# 3DHover.net
KiCad netlist of a schematic drawn in EAGLE
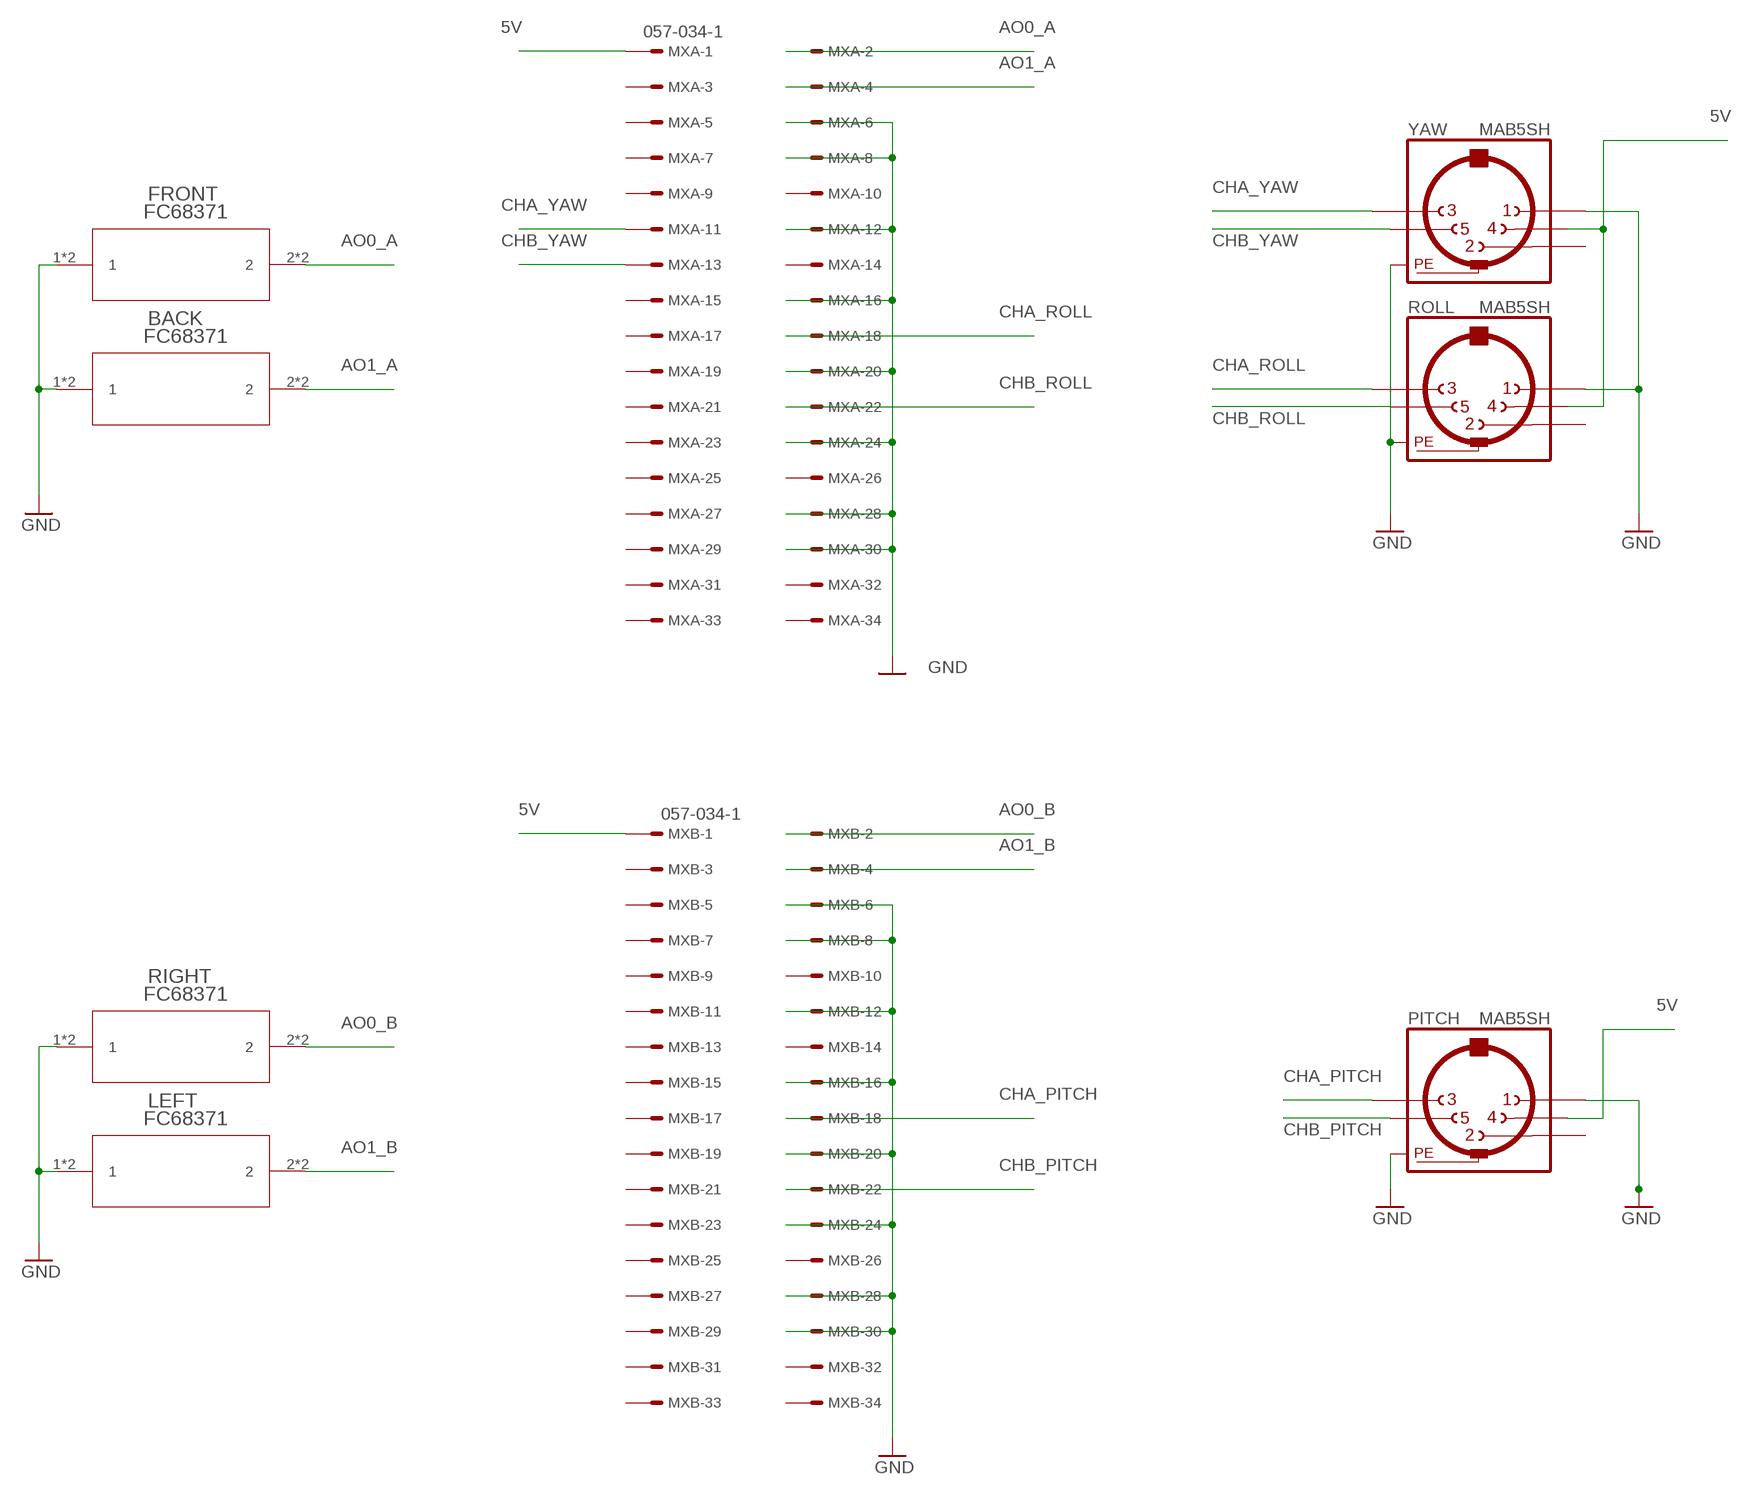
[diagram p0: schematic, sheet 1]

(export (version "E")
  (design (tool "Eeschema 10.0.6"))
  (components
    (comp (ref "BACK")
      (value "FC68371")
      (footprint "eagle-import:FC68371_CLF")
      (fields (field (name "COPYRIGHT") "Copyright (C) 2022 Ultra Librarian. All rights reserved."))
      (libsource (lib "eagle-import") (part "FC68371"))
    )
    (comp (ref "FRONT")
      (value "FC68371")
      (footprint "eagle-import:FC68371_CLF")
      (fields (field (name "COPYRIGHT") "Copyright (C) 2022 Ultra Librarian. All rights reserved."))
      (libsource (lib "eagle-import") (part "FC68371"))
    )
    (comp (ref "LEFT")
      (value "FC68371")
      (footprint "eagle-import:FC68371_CLF")
      (fields (field (name "COPYRIGHT") "Copyright (C) 2022 Ultra Librarian. All rights reserved."))
      (libsource (lib "eagle-import") (part "FC68371"))
    )
    (comp (ref "MXA")
      (value "057-034-1")
      (footprint "eagle-import:057-034-1")
      (libsource (lib "eagle-import") (part "057-034-1"))
    )
    (comp (ref "MXB")
      (value "057-034-1")
      (footprint "eagle-import:057-034-1")
      (libsource (lib "eagle-import") (part "057-034-1"))
    )
    (comp (ref "PITCH")
      (value "MAB5SH")
      (footprint "eagle-import:MAB5SH")
      (libsource (lib "eagle-import") (part "MAB5SH"))
    )
    (comp (ref "RIGHT")
      (value "FC68371")
      (footprint "eagle-import:FC68371_CLF")
      (fields (field (name "COPYRIGHT") "Copyright (C) 2022 Ultra Librarian. All rights reserved."))
      (libsource (lib "eagle-import") (part "FC68371"))
    )
    (comp (ref "ROLL")
      (value "MAB5SH")
      (footprint "eagle-import:MAB5SH")
      (libsource (lib "eagle-import") (part "MAB5SH"))
    )
    (comp (ref "YAW")
      (value "MAB5SH")
      (footprint "eagle-import:MAB5SH")
      (libsource (lib "eagle-import") (part "MAB5SH"))
    )
  )
  (nets
    (net (code "1") (name "/5V") (class "Default")
      (node (ref "MXA") (pin "1") (pinfunction "S_1") (pintype "passive"))
      (node (ref "MXB") (pin "1") (pinfunction "S_1") (pintype "passive"))
      (node (ref "PITCH") (pin "4") (pinfunction "4_4") (pintype "passive"))
      (node (ref "ROLL") (pin "4") (pinfunction "4_4") (pintype "passive"))
      (node (ref "YAW") (pin "4") (pinfunction "4_4") (pintype "passive"))
    )
    (net (code "2") (name "/AO0_A") (class "Default")
      (node (ref "FRONT") (pin "2") (pinfunction "2_2") (pintype "passive"))
      (node (ref "FRONT") (pin "4") (pinfunction "2_4") (pintype "passive"))
      (node (ref "MXA") (pin "2") (pinfunction "S_2") (pintype "passive"))
    )
    (net (code "3") (name "/AO0_B") (class "Default")
      (node (ref "MXB") (pin "2") (pinfunction "S_2") (pintype "passive"))
      (node (ref "RIGHT") (pin "2") (pinfunction "2_2") (pintype "passive"))
      (node (ref "RIGHT") (pin "4") (pinfunction "2_4") (pintype "passive"))
    )
    (net (code "4") (name "/AO1_A") (class "Default")
      (node (ref "BACK") (pin "2") (pinfunction "2_2") (pintype "passive"))
      (node (ref "BACK") (pin "4") (pinfunction "2_4") (pintype "passive"))
      (node (ref "MXA") (pin "4") (pinfunction "S_4") (pintype "passive"))
    )
    (net (code "5") (name "/AO1_B") (class "Default")
      (node (ref "LEFT") (pin "2") (pinfunction "2_2") (pintype "passive"))
      (node (ref "LEFT") (pin "4") (pinfunction "2_4") (pintype "passive"))
      (node (ref "MXB") (pin "4") (pinfunction "S_4") (pintype "passive"))
    )
    (net (code "6") (name "/CHA_PITCH") (class "Default")
      (node (ref "MXB") (pin "18") (pinfunction "S_18") (pintype "passive"))
      (node (ref "PITCH") (pin "3") (pinfunction "3_3") (pintype "passive"))
    )
    (net (code "7") (name "/CHA_ROLL") (class "Default")
      (node (ref "MXA") (pin "18") (pinfunction "S_18") (pintype "passive"))
      (node (ref "ROLL") (pin "3") (pinfunction "3_3") (pintype "passive"))
    )
    (net (code "8") (name "/CHA_YAW") (class "Default")
      (node (ref "MXA") (pin "11") (pinfunction "S_11") (pintype "passive"))
      (node (ref "YAW") (pin "3") (pinfunction "3_3") (pintype "passive"))
    )
    (net (code "9") (name "/CHB_PITCH") (class "Default")
      (node (ref "MXB") (pin "22") (pinfunction "S_22") (pintype "passive"))
      (node (ref "PITCH") (pin "5") (pinfunction "5_5") (pintype "passive"))
    )
    (net (code "10") (name "/CHB_ROLL") (class "Default")
      (node (ref "MXA") (pin "22") (pinfunction "S_22") (pintype "passive"))
      (node (ref "ROLL") (pin "5") (pinfunction "5_5") (pintype "passive"))
    )
    (net (code "11") (name "/CHB_YAW") (class "Default")
      (node (ref "MXA") (pin "13") (pinfunction "S_13") (pintype "passive"))
      (node (ref "YAW") (pin "5") (pinfunction "5_5") (pintype "passive"))
    )
    (net (code "12") (name "GND") (class "Default")
      (node (ref "BACK") (pin "1") (pinfunction "1_1") (pintype "passive"))
      (node (ref "BACK") (pin "3") (pinfunction "1_3") (pintype "passive"))
      (node (ref "FRONT") (pin "1") (pinfunction "1_1") (pintype "passive"))
      (node (ref "FRONT") (pin "3") (pinfunction "1_3") (pintype "passive"))
      (node (ref "LEFT") (pin "1") (pinfunction "1_1") (pintype "passive"))
      (node (ref "LEFT") (pin "3") (pinfunction "1_3") (pintype "passive"))
      (node (ref "MXA") (pin "12") (pinfunction "S_12") (pintype "passive"))
      (node (ref "MXA") (pin "16") (pinfunction "S_16") (pintype "passive"))
      (node (ref "MXA") (pin "20") (pinfunction "S_20") (pintype "passive"))
      (node (ref "MXA") (pin "24") (pinfunction "S_24") (pintype "passive"))
      (node (ref "MXA") (pin "28") (pinfunction "S_28") (pintype "passive"))
      (node (ref "MXA") (pin "30") (pinfunction "S_30") (pintype "passive"))
      (node (ref "MXA") (pin "6") (pinfunction "S_6") (pintype "passive"))
      (node (ref "MXA") (pin "8") (pinfunction "S_8") (pintype "passive"))
      (node (ref "MXB") (pin "12") (pinfunction "S_12") (pintype "passive"))
      (node (ref "MXB") (pin "16") (pinfunction "S_16") (pintype "passive"))
      (node (ref "MXB") (pin "20") (pinfunction "S_20") (pintype "passive"))
      (node (ref "MXB") (pin "24") (pinfunction "S_24") (pintype "passive"))
      (node (ref "MXB") (pin "28") (pinfunction "S_28") (pintype "passive"))
      (node (ref "MXB") (pin "30") (pinfunction "S_30") (pintype "passive"))
      (node (ref "MXB") (pin "6") (pinfunction "S_6") (pintype "passive"))
      (node (ref "MXB") (pin "8") (pinfunction "S_8") (pintype "passive"))
      (node (ref "PITCH") (pin "1") (pinfunction "1_1") (pintype "passive"))
      (node (ref "PITCH") (pin "PE") (pinfunction "PE_PE") (pintype "power_in"))
      (node (ref "PITCH") (pin "PE@") (pinfunction "PE_PE@") (pintype "power_in"))
      (node (ref "RIGHT") (pin "1") (pinfunction "1_1") (pintype "passive"))
      (node (ref "RIGHT") (pin "3") (pinfunction "1_3") (pintype "passive"))
      (node (ref "ROLL") (pin "1") (pinfunction "1_1") (pintype "passive"))
      (node (ref "ROLL") (pin "PE") (pinfunction "PE_PE") (pintype "power_in"))
      (node (ref "ROLL") (pin "PE@") (pinfunction "PE_PE@") (pintype "power_in"))
      (node (ref "YAW") (pin "1") (pinfunction "1_1") (pintype "passive"))
      (node (ref "YAW") (pin "PE") (pinfunction "PE_PE") (pintype "power_in"))
      (node (ref "YAW") (pin "PE@") (pinfunction "PE_PE@") (pintype "power_in"))
    )
    (net (code "13") (name "unconnected-(MXAAA-S-Pad33)") (class "Default")
      (node (ref "MXA") (pin "33") (pinfunction "S_33") (pintype "passive"))
    )
    (net (code "14") (name "unconnected-(MXAAB-S-Pad34)") (class "Default")
      (node (ref "MXA") (pin "34") (pinfunction "S_34") (pintype "passive"))
    )
    (net (code "15") (name "unconnected-(MXAAD-S-Pad5)") (class "Default")
      (node (ref "MXA") (pin "5") (pinfunction "S_5") (pintype "passive"))
    )
    (net (code "16") (name "unconnected-(MXAAF-S-Pad7)") (class "Default")
      (node (ref "MXA") (pin "7") (pinfunction "S_7") (pintype "passive"))
    )
    (net (code "17") (name "unconnected-(MXAAH-S-Pad9)") (class "Default")
      (node (ref "MXA") (pin "9") (pinfunction "S_9") (pintype "passive"))
    )
    (net (code "18") (name "unconnected-(MXAB-S-Pad10)") (class "Default")
      (node (ref "MXA") (pin "10") (pinfunction "S_10") (pintype "passive"))
    )
    (net (code "19") (name "unconnected-(MXAF-S-Pad14)") (class "Default")
      (node (ref "MXA") (pin "14") (pinfunction "S_14") (pintype "passive"))
    )
    (net (code "20") (name "unconnected-(MXAG-S-Pad15)") (class "Default")
      (node (ref "MXA") (pin "15") (pinfunction "S_15") (pintype "passive"))
    )
    (net (code "21") (name "unconnected-(MXAI-S-Pad17)") (class "Default")
      (node (ref "MXA") (pin "17") (pinfunction "S_17") (pintype "passive"))
    )
    (net (code "22") (name "unconnected-(MXAK-S-Pad19)") (class "Default")
      (node (ref "MXA") (pin "19") (pinfunction "S_19") (pintype "passive"))
    )
    (net (code "23") (name "unconnected-(MXAN-S-Pad21)") (class "Default")
      (node (ref "MXA") (pin "21") (pinfunction "S_21") (pintype "passive"))
    )
    (net (code "24") (name "unconnected-(MXAP-S-Pad23)") (class "Default")
      (node (ref "MXA") (pin "23") (pinfunction "S_23") (pintype "passive"))
    )
    (net (code "25") (name "unconnected-(MXAR-S-Pad25)") (class "Default")
      (node (ref "MXA") (pin "25") (pinfunction "S_25") (pintype "passive"))
    )
    (net (code "26") (name "unconnected-(MXAS-S-Pad26)") (class "Default")
      (node (ref "MXA") (pin "26") (pinfunction "S_26") (pintype "passive"))
    )
    (net (code "27") (name "unconnected-(MXAT-S-Pad27)") (class "Default")
      (node (ref "MXA") (pin "27") (pinfunction "S_27") (pintype "passive"))
    )
    (net (code "28") (name "unconnected-(MXAV-S-Pad29)") (class "Default")
      (node (ref "MXA") (pin "29") (pinfunction "S_29") (pintype "passive"))
    )
    (net (code "29") (name "unconnected-(MXAW-S-Pad3)") (class "Default")
      (node (ref "MXA") (pin "3") (pinfunction "S_3") (pintype "passive"))
    )
    (net (code "30") (name "unconnected-(MXAY-S-Pad31)") (class "Default")
      (node (ref "MXA") (pin "31") (pinfunction "S_31") (pintype "passive"))
    )
    (net (code "31") (name "unconnected-(MXAZ-S-Pad32)") (class "Default")
      (node (ref "MXA") (pin "32") (pinfunction "S_32") (pintype "passive"))
    )
    (net (code "32") (name "unconnected-(MXBAA-S-Pad33)") (class "Default")
      (node (ref "MXB") (pin "33") (pinfunction "S_33") (pintype "passive"))
    )
    (net (code "33") (name "unconnected-(MXBAB-S-Pad34)") (class "Default")
      (node (ref "MXB") (pin "34") (pinfunction "S_34") (pintype "passive"))
    )
    (net (code "34") (name "unconnected-(MXBAD-S-Pad5)") (class "Default")
      (node (ref "MXB") (pin "5") (pinfunction "S_5") (pintype "passive"))
    )
    (net (code "35") (name "unconnected-(MXBAF-S-Pad7)") (class "Default")
      (node (ref "MXB") (pin "7") (pinfunction "S_7") (pintype "passive"))
    )
    (net (code "36") (name "unconnected-(MXBAH-S-Pad9)") (class "Default")
      (node (ref "MXB") (pin "9") (pinfunction "S_9") (pintype "passive"))
    )
    (net (code "37") (name "unconnected-(MXBB-S-Pad10)") (class "Default")
      (node (ref "MXB") (pin "10") (pinfunction "S_10") (pintype "passive"))
    )
    (net (code "38") (name "unconnected-(MXBC-S-Pad11)") (class "Default")
      (node (ref "MXB") (pin "11") (pinfunction "S_11") (pintype "passive"))
    )
    (net (code "39") (name "unconnected-(MXBE-S-Pad13)") (class "Default")
      (node (ref "MXB") (pin "13") (pinfunction "S_13") (pintype "passive"))
    )
    (net (code "40") (name "unconnected-(MXBF-S-Pad14)") (class "Default")
      (node (ref "MXB") (pin "14") (pinfunction "S_14") (pintype "passive"))
    )
    (net (code "41") (name "unconnected-(MXBG-S-Pad15)") (class "Default")
      (node (ref "MXB") (pin "15") (pinfunction "S_15") (pintype "passive"))
    )
    (net (code "42") (name "unconnected-(MXBI-S-Pad17)") (class "Default")
      (node (ref "MXB") (pin "17") (pinfunction "S_17") (pintype "passive"))
    )
    (net (code "43") (name "unconnected-(MXBK-S-Pad19)") (class "Default")
      (node (ref "MXB") (pin "19") (pinfunction "S_19") (pintype "passive"))
    )
    (net (code "44") (name "unconnected-(MXBN-S-Pad21)") (class "Default")
      (node (ref "MXB") (pin "21") (pinfunction "S_21") (pintype "passive"))
    )
    (net (code "45") (name "unconnected-(MXBP-S-Pad23)") (class "Default")
      (node (ref "MXB") (pin "23") (pinfunction "S_23") (pintype "passive"))
    )
    (net (code "46") (name "unconnected-(MXBR-S-Pad25)") (class "Default")
      (node (ref "MXB") (pin "25") (pinfunction "S_25") (pintype "passive"))
    )
    (net (code "47") (name "unconnected-(MXBS-S-Pad26)") (class "Default")
      (node (ref "MXB") (pin "26") (pinfunction "S_26") (pintype "passive"))
    )
    (net (code "48") (name "unconnected-(MXBT-S-Pad27)") (class "Default")
      (node (ref "MXB") (pin "27") (pinfunction "S_27") (pintype "passive"))
    )
    (net (code "49") (name "unconnected-(MXBV-S-Pad29)") (class "Default")
      (node (ref "MXB") (pin "29") (pinfunction "S_29") (pintype "passive"))
    )
    (net (code "50") (name "unconnected-(MXBW-S-Pad3)") (class "Default")
      (node (ref "MXB") (pin "3") (pinfunction "S_3") (pintype "passive"))
    )
    (net (code "51") (name "unconnected-(MXBY-S-Pad31)") (class "Default")
      (node (ref "MXB") (pin "31") (pinfunction "S_31") (pintype "passive"))
    )
    (net (code "52") (name "unconnected-(MXBZ-S-Pad32)") (class "Default")
      (node (ref "MXB") (pin "32") (pinfunction "S_32") (pintype "passive"))
    )
    (net (code "53") (name "unconnected-(PITCH-Pad2)") (class "Default")
      (node (ref "PITCH") (pin "2") (pinfunction "2_2") (pintype "passive"))
    )
    (net (code "54") (name "unconnected-(ROLL-Pad2)") (class "Default")
      (node (ref "ROLL") (pin "2") (pinfunction "2_2") (pintype "passive"))
    )
    (net (code "55") (name "unconnected-(YAW-Pad2)") (class "Default")
      (node (ref "YAW") (pin "2") (pinfunction "2_2") (pintype "passive"))
    )
  )
)
